# connections.net
KiCad netlist of a schematic drawn in Altium Designer
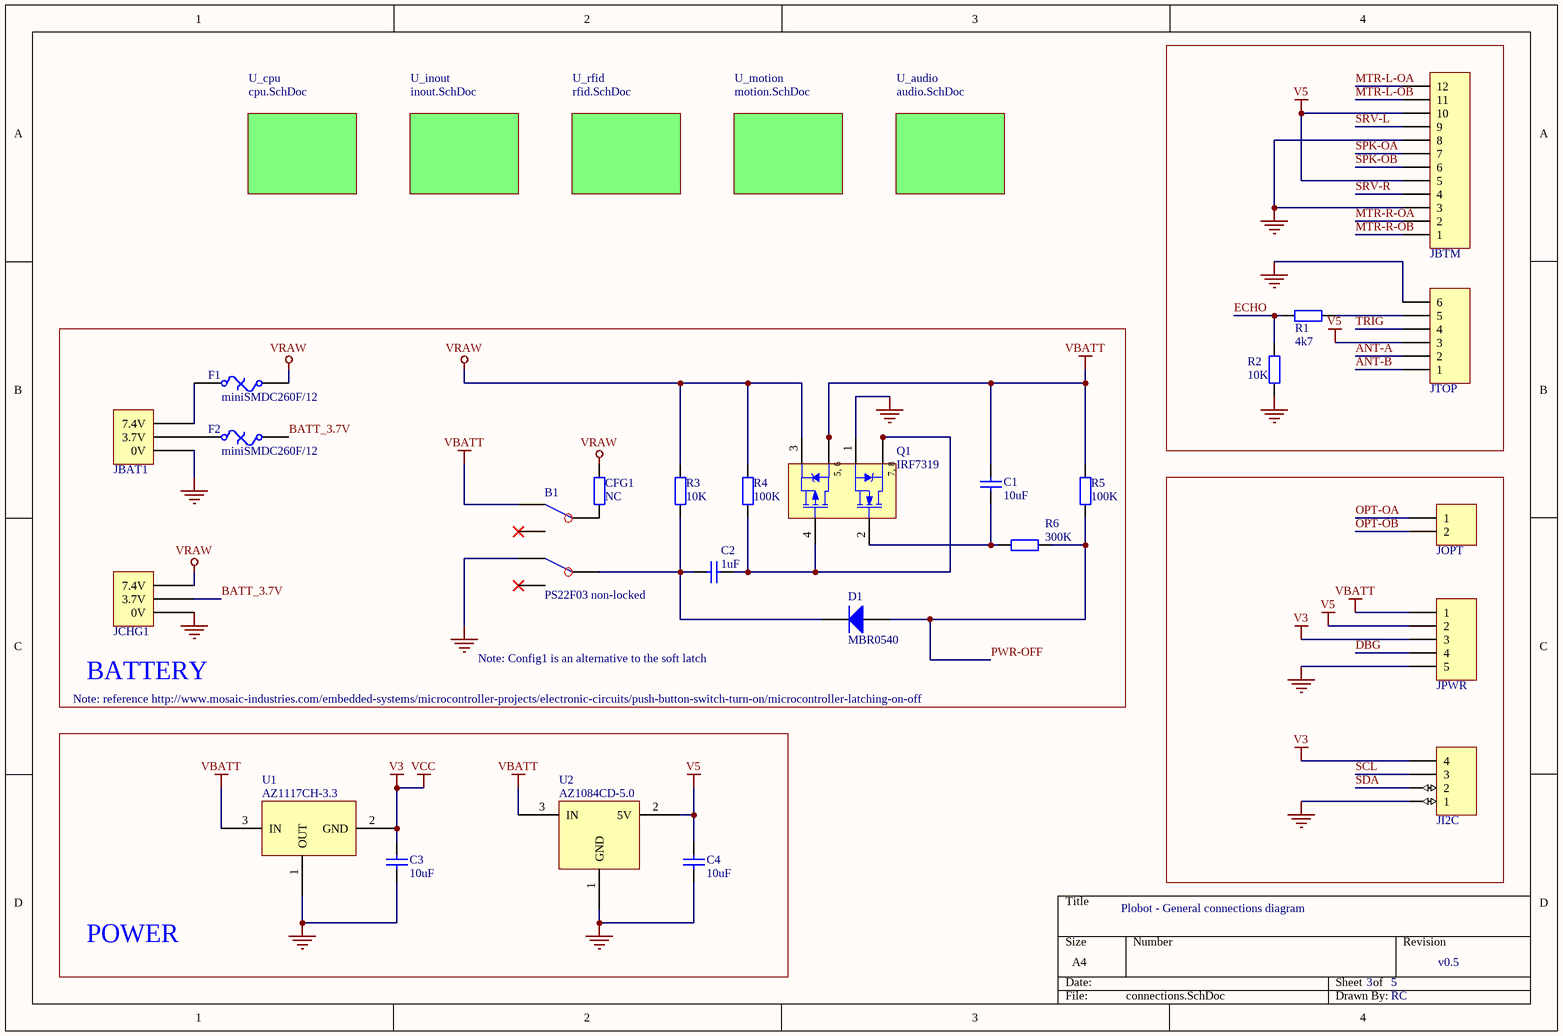
[diagram p0: connections.SchDoc]

(export (version "E")
  (design (tool "Eeschema 10.0.6"))
  (components
    (comp (ref "B1")
      (value "PS22F03 non-locked")
      (footprint "plobot_review:KGPS22F03")
      (libsource (lib "*") (part "Component_1"))
    )
    (comp (ref "C1")
      (value "10uF")
      (footprint "plobot_review:CAPC3216N")
      (description "Capacitor")
      (libsource (lib "main_pcb") (part "Cap_2"))
    )
    (comp (ref "C2")
      (value "1uF")
      (footprint "plobot_review:CAPC3216N")
      (description "Capacitor")
      (libsource (lib "main_pcb") (part "Cap_2"))
    )
    (comp (ref "C3")
      (value "10uF")
      (footprint "plobot_review:CAPC3216N")
      (description "Capacitor")
      (fields (field (name "PUBLISHER") "Altium Limited"))
      (libsource (lib "main_pcb") (part "Cap_2"))
    )
    (comp (ref "C4")
      (value "10uF")
      (footprint "plobot_review:CAPC3216N")
      (description "Capacitor")
      (fields (field (name "PUBLISHER") "Altium Limited"))
      (libsource (lib "main_pcb") (part "Cap_2"))
    )
    (comp (ref "CFG1")
      (value "NC")
      (footprint "plobot_review:RESC1608N")
      (description "Resistor")
      (libsource (lib "") (part "Res2_1"))
    )
    (comp (ref "D1")
      (value "MBR0540")
      (footprint "plobot_review:SOD123/X.85")
      (description "Default Diode")
      (libsource (lib "Miscellaneous Devices") (part "Diode"))
    )
    (comp (ref "F1")
      (value "miniSMDC260F/12")
      (footprint "plobot_review:miniSMDC260F/12")
      (description "Thermal Fuse")
      (fields (field (name "PUBLISHER") "Altium Limited"))
      (libsource (lib "Miscellaneous Devices") (part "Fuse Thermal"))
    )
    (comp (ref "F2")
      (value "miniSMDC260F/12")
      (footprint "plobot_review:miniSMDC260F/12")
      (description "Thermal Fuse")
      (fields (field (name "PUBLISHER") "Altium Limited"))
      (libsource (lib "Miscellaneous Devices") (part "Fuse Thermal"))
    )
    (comp (ref "JBAT1")
      (value "Charger")
      (footprint "plobot_review:S3B-XH-A(LF)(SN)")
      (libsource (lib "components") (part "BATTCON"))
    )
    (comp (ref "JBTM")
      (value "Header 12")
      (footprint "plobot_review:JST-B12B-XH")
      (description "Header, 12-Pin")
      (libsource (lib "Miscellaneous Connectors") (part "Header 12"))
    )
    (comp (ref "JCHG1")
      (value "Charger")
      (footprint "plobot_review:S3B-XH-A( FEMALE )")
      (libsource (lib "components") (part "BATTCON"))
    )
    (comp (ref "JI2C")
      (value "Header 4")
      (footprint "plobot_review:HDR1X4")
      (description "Header, 4-Pin")
      (libsource (lib "Miscellaneous Connectors") (part "Header 4"))
    )
    (comp (ref "JOPT")
      (value "Header 2")
      (footprint "HDR1X2")
      (description "Header, 2-Pin")
      (fields (field (name "PUBLISHER") "Altium Limited"))
      (libsource (lib "Miscellaneous Connectors") (part "Header 2"))
    )
    (comp (ref "JPWR")
      (value "Component")
      (footprint "HDR1X5")
      (description "Header, 5-Pin")
      (fields (field (name "PUBLISHER") "Altium Limited"))
      (libsource (lib "Miscellaneous Connectors") (part "Header 5"))
    )
    (comp (ref "JTOP")
      (value "w/lock")
      (footprint "plobot_review:JST-B6B-XH")
      (description "Header, 6-Pin")
      (libsource (lib "Miscellaneous Connectors") (part "Header 6"))
    )
    (comp (ref "Q1")
      (value "IRF7319")
      (footprint "plobot_review:SO-8_L")
      (description "HEXFET Power MOSFET")
      (libsource (lib "IR Discrete MOSFET - Power") (part "IRF7319"))
    )
    (comp (ref "R1")
      (value "4k7")
      (footprint "plobot_review:RESC1608N")
      (description "Resistor")
      (fields (field (name "Comment") "10k") (field (name "PUBLISHER") "Altium Limited"))
      (libsource (lib "") (part "Res2_3"))
    )
    (comp (ref "R2")
      (value "10K")
      (footprint "plobot_review:RESC1608N")
      (description "Resistor")
      (fields (field (name "PUBLISHER") "Altium Limited"))
      (libsource (lib "") (part "Res2_1"))
    )
    (comp (ref "R3")
      (value "10K")
      (footprint "plobot_review:RESC1608N")
      (description "Resistor")
      (libsource (lib "") (part "Res2_2"))
    )
    (comp (ref "R4")
      (value "100K")
      (footprint "plobot_review:RESC1608N")
      (description "Resistor")
      (libsource (lib "") (part "Res2_2"))
    )
    (comp (ref "R5")
      (value "100K")
      (footprint "plobot_review:RESC1608N")
      (description "Resistor")
      (libsource (lib "") (part "Res2_2"))
    )
    (comp (ref "R6")
      (value "300K")
      (footprint "plobot_review:RESC1608N")
      (description "Resistor")
      (libsource (lib "*") (part "Res2"))
    )
    (comp (ref "U1")
      (value "AZ1117CH-3.3")
      (footprint "plobot_review:SOT223")
      (libsource (lib "*") (part "LM1117"))
    )
    (comp (ref "U2")
      (value "AZ1084CD-5.0")
      (footprint "plobot_review:AZ1084CD-5.0")
      (libsource (lib "components") (part "AZ1084CD-5.0"))
    )
  )
  (nets
    (net (code "1") (name "/ANT-A") (class "Default")
      (node (ref "JTOP") (pin "2") (pinfunction "2_2") (pintype "passive"))
    )
    (net (code "2") (name "/ANT-B") (class "Default")
      (node (ref "JTOP") (pin "1") (pinfunction "1_1") (pintype "passive"))
    )
    (net (code "3") (name "/BATT_3.7V") (class "Default")
      (node (ref "F2") (pin "2") (pinfunction "2_2") (pintype "passive"))
      (node (ref "JCHG1") (pin "2") (pinfunction "3.7V_2") (pintype "passive"))
    )
    (net (code "4") (name "/DBG") (class "Default")
      (node (ref "JPWR") (pin "4") (pinfunction "4_4") (pintype "passive"))
    )
    (net (code "5") (name "/ECHO") (class "Default")
      (node (ref "R1") (pin "1") (pinfunction "1_1") (pintype "passive"))
      (node (ref "R2") (pin "1") (pinfunction "1_1") (pintype "passive"))
    )
    (net (code "6") (name "/MTR-L-OA") (class "Default")
      (node (ref "JBTM") (pin "12") (pinfunction "12_12") (pintype "passive"))
    )
    (net (code "7") (name "/MTR-L-OB") (class "Default")
      (node (ref "JBTM") (pin "11") (pinfunction "11_11") (pintype "passive"))
    )
    (net (code "8") (name "/MTR-R-OA") (class "Default")
      (node (ref "JBTM") (pin "2") (pinfunction "2_2") (pintype "passive"))
    )
    (net (code "9") (name "/MTR-R-OB") (class "Default")
      (node (ref "JBTM") (pin "1") (pinfunction "1_1") (pintype "passive"))
    )
    (net (code "10") (name "/OPT-OA") (class "Default")
      (node (ref "JOPT") (pin "1") (pinfunction "1_1") (pintype "passive"))
    )
    (net (code "11") (name "/OPT-OB") (class "Default")
      (node (ref "JOPT") (pin "2") (pinfunction "2_2") (pintype "passive"))
    )
    (net (code "12") (name "/PWR-OFF") (class "Default")
      (node (ref "D1") (pin "2") (pinfunction "A_2") (pintype "passive"))
      (node (ref "R5") (pin "1") (pinfunction "1_1") (pintype "passive"))
      (node (ref "R6") (pin "1") (pinfunction "1_1") (pintype "passive"))
    )
    (net (code "13") (name "/SCL") (class "Default")
      (node (ref "JI2C") (pin "3") (pinfunction "3_3") (pintype "power_in"))
    )
    (net (code "14") (name "/SDA") (class "Default")
      (node (ref "JI2C") (pin "2") (pinfunction "2_2") (pintype "bidirectional"))
    )
    (net (code "15") (name "/SPK-OA") (class "Default")
      (node (ref "JBTM") (pin "7") (pinfunction "7_7") (pintype "passive"))
    )
    (net (code "16") (name "/SPK-OB") (class "Default")
      (node (ref "JBTM") (pin "6") (pinfunction "6_6") (pintype "passive"))
    )
    (net (code "17") (name "/SRV-L") (class "Default")
      (node (ref "JBTM") (pin "9") (pinfunction "9_9") (pintype "passive"))
    )
    (net (code "18") (name "/SRV-R") (class "Default")
      (node (ref "JBTM") (pin "4") (pinfunction "4_4") (pintype "passive"))
    )
    (net (code "19") (name "/TRIG") (class "Default")
      (node (ref "JTOP") (pin "4") (pinfunction "4_4") (pintype "passive"))
    )
    (net (code "20") (name "GND") (class "Default")
      (node (ref "B1") (pin "4") (pintype "passive"))
      (node (ref "C3") (pin "2") (pinfunction "2_2") (pintype "passive"))
      (node (ref "C4") (pin "1") (pinfunction "1_1") (pintype "passive"))
      (node (ref "JBAT1") (pin "1") (pinfunction "0V_1") (pintype "passive"))
      (node (ref "JBTM") (pin "3") (pinfunction "3_3") (pintype "passive"))
      (node (ref "JBTM") (pin "8") (pinfunction "8_8") (pintype "passive"))
      (node (ref "JCHG1") (pin "1") (pinfunction "0V_1") (pintype "passive"))
      (node (ref "JI2C") (pin "1") (pinfunction "1_1") (pintype "bidirectional"))
      (node (ref "JPWR") (pin "5") (pinfunction "5_5") (pintype "passive"))
      (node (ref "JTOP") (pin "6") (pinfunction "6_6") (pintype "passive"))
      (node (ref "Q1") (pin "1") (pinfunction "S1_1") (pintype "passive"))
      (node (ref "R2") (pin "2") (pinfunction "2_2") (pintype "passive"))
      (node (ref "U1") (pin "1") (pinfunction "OUT_1") (pintype "passive"))
      (node (ref "U2") (pin "1") (pinfunction "GND_1") (pintype "passive"))
    )
    (net (code "21") (name "Net-(B1-Pad2)") (class "Default")
      (node (ref "B1") (pin "2") (pintype "passive"))
      (node (ref "CFG1") (pin "2") (pinfunction "2_2") (pintype "passive"))
    )
    (net (code "22") (name "Net-(D1-K)") (class "Default")
      (node (ref "B1") (pin "5") (pintype "passive"))
      (node (ref "C2") (pin "1") (pinfunction "1_1") (pintype "passive"))
      (node (ref "D1") (pin "1") (pinfunction "K_1") (pintype "passive"))
      (node (ref "R3") (pin "1") (pinfunction "1_1") (pintype "passive"))
    )
    (net (code "23") (name "Net-(JBAT1-3.7V)") (class "Default")
      (node (ref "F2") (pin "1") (pinfunction "1_1") (pintype "passive"))
      (node (ref "JBAT1") (pin "2") (pinfunction "3.7V_2") (pintype "passive"))
    )
    (net (code "24") (name "Net-(JBAT1-7.4V)") (class "Default")
      (node (ref "F1") (pin "1") (pinfunction "1_1") (pintype "passive"))
      (node (ref "JBAT1") (pin "3") (pinfunction "7.4V_3") (pintype "passive"))
    )
    (net (code "25") (name "Net-(JTOP-Pad5)") (class "Default")
      (node (ref "JTOP") (pin "5") (pinfunction "5_5") (pintype "passive"))
      (node (ref "R1") (pin "2") (pinfunction "2_2") (pintype "passive"))
    )
    (net (code "26") (name "Net-(Q1-G1)") (class "Default")
      (node (ref "C1") (pin "2") (pinfunction "2_2") (pintype "passive"))
      (node (ref "Q1") (pin "2") (pinfunction "G1_2") (pintype "passive"))
      (node (ref "R6") (pin "2") (pinfunction "2_2") (pintype "passive"))
    )
    (net (code "27") (name "Net-(Q1-G2)") (class "Default")
      (node (ref "C2") (pin "2") (pinfunction "2_2") (pintype "passive"))
      (node (ref "Q1") (pin "4") (pinfunction "G2_4") (pintype "passive"))
      (node (ref "Q1") (pin "7") (pinfunction "D1_7") (pintype "passive"))
      (node (ref "Q1") (pin "8") (pinfunction "D1_8") (pintype "passive"))
      (node (ref "R4") (pin "1") (pinfunction "1_1") (pintype "passive"))
    )
    (net (code "28") (name "V3") (class "Default")
      (node (ref "C3") (pin "1") (pinfunction "1_1") (pintype "passive"))
      (node (ref "JI2C") (pin "4") (pinfunction "4_4") (pintype "power_in"))
      (node (ref "JPWR") (pin "3") (pinfunction "3_3") (pintype "passive"))
      (node (ref "U1") (pin "2") (pinfunction "GND_2") (pintype "passive"))
    )
    (net (code "29") (name "V5") (class "Default")
      (node (ref "C4") (pin "2") (pinfunction "2_2") (pintype "passive"))
      (node (ref "JBTM") (pin "10") (pinfunction "10_10") (pintype "passive"))
      (node (ref "JBTM") (pin "5") (pinfunction "5_5") (pintype "passive"))
      (node (ref "JPWR") (pin "2") (pinfunction "2_2") (pintype "passive"))
      (node (ref "JTOP") (pin "3") (pinfunction "3_3") (pintype "passive"))
      (node (ref "U2") (pin "2") (pinfunction "5V_2") (pintype "passive"))
    )
    (net (code "30") (name "VBATT") (class "Default")
      (node (ref "B1") (pin "3") (pintype "passive"))
      (node (ref "C1") (pin "1") (pinfunction "1_1") (pintype "passive"))
      (node (ref "JPWR") (pin "1") (pinfunction "1_1") (pintype "passive"))
      (node (ref "Q1") (pin "5") (pinfunction "D2_5") (pintype "passive"))
      (node (ref "Q1") (pin "6") (pinfunction "D2_6") (pintype "passive"))
      (node (ref "R5") (pin "2") (pinfunction "2_2") (pintype "passive"))
      (node (ref "U1") (pin "3") (pinfunction "IN_3") (pintype "passive"))
      (node (ref "U2") (pin "3") (pinfunction "IN_3") (pintype "passive"))
    )
    (net (code "31") (name "VRAW") (class "Default")
      (node (ref "CFG1") (pin "1") (pinfunction "1_1") (pintype "passive"))
      (node (ref "F1") (pin "2") (pinfunction "2_2") (pintype "passive"))
      (node (ref "JCHG1") (pin "3") (pinfunction "7.4V_3") (pintype "passive"))
      (node (ref "Q1") (pin "3") (pinfunction "S2_3") (pintype "passive"))
      (node (ref "R3") (pin "2") (pinfunction "2_2") (pintype "passive"))
      (node (ref "R4") (pin "2") (pinfunction "2_2") (pintype "passive"))
    )
    (net (code "32") (name "unconnected-(B1-Pad1)") (class "Default")
      (node (ref "B1") (pin "1") (pintype "passive+no_connect"))
    )
    (net (code "33") (name "unconnected-(B1-Pad6)") (class "Default")
      (node (ref "B1") (pin "6") (pintype "passive+no_connect"))
    )
  )
)
